# Placa_1.net
KiCad netlist of a schematic drawn in EAGLE
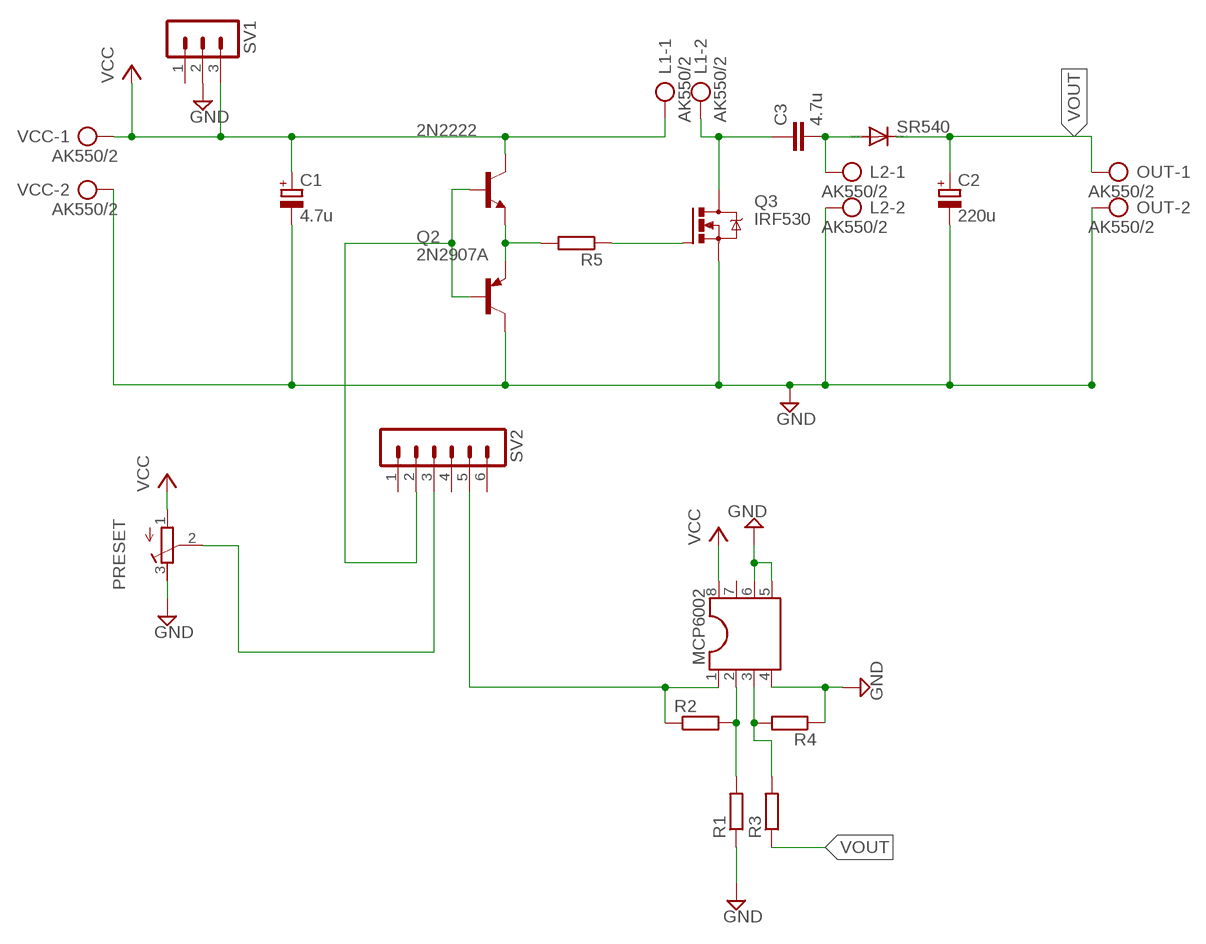
[diagram p0: schematic, sheet 1]

(export (version "E")
  (design (tool "Eeschema 10.0.6"))
  (components
    (comp (ref "2N2222")
      (value "2N2222-NPN-TO92-EBC")
      (footprint "eagle-import:TO92-EBC")
      (libsource (lib "eagle-import") (part "-NPN-TO92-EBC2N2222"))
    )
    (comp (ref "C1")
      (value "4.7u")
      (footprint "eagle-import:E5-8,5")
      (libsource (lib "eagle-import") (part "CPOL-EUE5-8.5"))
    )
    (comp (ref "C2")
      (value "220u")
      (footprint "eagle-import:E5-8,5")
      (libsource (lib "eagle-import") (part "CPOL-EUE5-8.5"))
    )
    (comp (ref "C3")
      (value "4.7u")
      (footprint "eagle-import:C075-052X106")
      (libsource (lib "eagle-import") (part "C-EU075-052X106"))
    )
    (comp (ref "L1")
      (value "AK550/2")
      (footprint "eagle-import:AK550_2")
      (libsource (lib "eagle-import") (part "AK550/2"))
    )
    (comp (ref "L2")
      (value "AK550/2")
      (footprint "eagle-import:AK550_2")
      (libsource (lib "eagle-import") (part "AK550/2"))
    )
    (comp (ref "MCP6002")
      (value "DIL8")
      (footprint "eagle-import:DIL08")
      (libsource (lib "eagle-import") (part "DIL8"))
    )
    (comp (ref "OUT")
      (value "AK550/2")
      (footprint "eagle-import:AK550_2")
      (libsource (lib "eagle-import") (part "AK550/2"))
    )
    (comp (ref "PRESET")
      (value "R-TRIMM64W")
      (footprint "eagle-import:RTRIM64W")
      (libsource (lib "eagle-import") (part "R-TRIMM64W"))
    )
    (comp (ref "Q2")
      (value "2N2907A")
      (footprint "eagle-import:TO18")
      (libsource (lib "eagle-import") (part "2N2907A"))
    )
    (comp (ref "Q3")
      (value "IRF530")
      (footprint "eagle-import:TO220BV")
      (libsource (lib "eagle-import") (part "IRF530"))
    )
    (comp (ref "R1")
      (value "R-EU_0207/10")
      (footprint "eagle-import:0207_10")
      (libsource (lib "eagle-import") (part "R-EU_0207/10"))
    )
    (comp (ref "R2")
      (value "R-EU_0207/10")
      (footprint "eagle-import:0207_10")
      (libsource (lib "eagle-import") (part "R-EU_0207/10"))
    )
    (comp (ref "R3")
      (value "R-EU_0207/10")
      (footprint "eagle-import:0207_10")
      (libsource (lib "eagle-import") (part "R-EU_0207/10"))
    )
    (comp (ref "R4")
      (value "R-EU_0207/10")
      (footprint "eagle-import:0207_10")
      (libsource (lib "eagle-import") (part "R-EU_0207/10"))
    )
    (comp (ref "R5")
      (value "R-EU_0207/10")
      (footprint "eagle-import:0207_10")
      (libsource (lib "eagle-import") (part "R-EU_0207/10"))
    )
    (comp (ref "SR540")
      (value "DIODE-DO27-15")
      (footprint "eagle-import:DO27-15")
      (libsource (lib "eagle-import") (part "DIODE-DO27-15"))
    )
    (comp (ref "SV1")
      (value "MA03-1")
      (footprint "eagle-import:MA03-1")
      (libsource (lib "eagle-import") (part "MA03-1"))
    )
    (comp (ref "SV2")
      (value "MA06-1")
      (footprint "eagle-import:MA06-1")
      (libsource (lib "eagle-import") (part "MA06-1"))
    )
    (comp (ref "VCC")
      (value "AK550/2")
      (footprint "eagle-import:AK550_2")
      (libsource (lib "eagle-import") (part "AK550/2"))
    )
  )
  (nets
    (net (code "1") (name "GND") (class "Default")
      (node (ref "C1") (pin "-") (pinfunction "-_-") (pintype "passive"))
      (node (ref "C2") (pin "-") (pinfunction "-_-") (pintype "passive"))
      (node (ref "L2") (pin "2") (pinfunction "KL_2") (pintype "passive"))
      (node (ref "MCP6002") (pin "4") (pinfunction "4_4") (pintype "passive"))
      (node (ref "MCP6002") (pin "5") (pinfunction "5_5") (pintype "passive"))
      (node (ref "MCP6002") (pin "6") (pinfunction "6_6") (pintype "passive"))
      (node (ref "OUT") (pin "2") (pinfunction "KL_2") (pintype "passive"))
      (node (ref "PRESET") (pin "3") (pinfunction "E_3") (pintype "passive"))
      (node (ref "Q2") (pin "3") (pinfunction "C_3") (pintype "passive"))
      (node (ref "Q3") (pin "S") (pinfunction "S_S") (pintype "passive"))
      (node (ref "R1") (pin "1") (pinfunction "1_1") (pintype "passive"))
      (node (ref "R4") (pin "1") (pinfunction "1_1") (pintype "passive"))
      (node (ref "SV1") (pin "2") (pinfunction "2_2") (pintype "passive"))
      (node (ref "VCC") (pin "2") (pinfunction "KL_2") (pintype "passive"))
    )
    (net (code "2") (name "Net-(L1B-KL)") (class "Default")
      (node (ref "C3") (pin "1") (pinfunction "1_1") (pintype "passive"))
      (node (ref "L1") (pin "2") (pinfunction "KL_2") (pintype "passive"))
      (node (ref "Q3") (pin "D") (pinfunction "D_D") (pintype "passive"))
    )
    (net (code "3") (name "Net-(L2A-KL)") (class "Default")
      (node (ref "C3") (pin "2") (pinfunction "2_2") (pintype "passive"))
      (node (ref "L2") (pin "1") (pinfunction "KL_1") (pintype "passive"))
      (node (ref "SR540") (pin "A") (pinfunction "A_A") (pintype "passive"))
    )
    (net (code "4") (name "Net-(MCP6002-Pad1)") (class "Default")
      (node (ref "MCP6002") (pin "1") (pinfunction "1_1") (pintype "passive"))
      (node (ref "R2") (pin "1") (pinfunction "1_1") (pintype "passive"))
      (node (ref "SV2") (pin "5") (pinfunction "5_5") (pintype "passive"))
    )
    (net (code "5") (name "Net-(MCP6002-Pad2)") (class "Default")
      (node (ref "MCP6002") (pin "2") (pinfunction "2_2") (pintype "passive"))
      (node (ref "R1") (pin "2") (pinfunction "2_2") (pintype "passive"))
      (node (ref "R2") (pin "2") (pinfunction "2_2") (pintype "passive"))
    )
    (net (code "6") (name "Net-(MCP6002-Pad3)") (class "Default")
      (node (ref "MCP6002") (pin "3") (pinfunction "3_3") (pintype "passive"))
      (node (ref "R3") (pin "2") (pinfunction "2_2") (pintype "passive"))
      (node (ref "R4") (pin "2") (pinfunction "2_2") (pintype "passive"))
    )
    (net (code "7") (name "Net-(PRESET-S)") (class "Default")
      (node (ref "PRESET") (pin "2") (pinfunction "S_2") (pintype "passive"))
      (node (ref "SV2") (pin "3") (pinfunction "3_3") (pintype "passive"))
    )
    (net (code "8") (name "Net-(Q2-B)") (class "Default")
      (node (ref "2N2222") (pin "B") (pinfunction "B_B") (pintype "passive"))
      (node (ref "Q2") (pin "2") (pinfunction "B_2") (pintype "passive"))
      (node (ref "SV2") (pin "2") (pinfunction "2_2") (pintype "passive"))
    )
    (net (code "9") (name "Net-(Q2-E)") (class "Default")
      (node (ref "2N2222") (pin "E") (pinfunction "E_E") (pintype "passive"))
      (node (ref "Q2") (pin "1") (pinfunction "E_1") (pintype "passive"))
      (node (ref "R5") (pin "2") (pinfunction "2_2") (pintype "passive"))
    )
    (net (code "10") (name "Net-(Q3-PadG)") (class "Default")
      (node (ref "Q3") (pin "G") (pinfunction "G_G") (pintype "passive"))
      (node (ref "R5") (pin "1") (pinfunction "1_1") (pintype "passive"))
    )
    (net (code "11") (name "VCC") (class "Default")
      (node (ref "2N2222") (pin "C") (pinfunction "C_C") (pintype "passive"))
      (node (ref "C1") (pin "+") (pinfunction "+_+") (pintype "passive"))
      (node (ref "L1") (pin "1") (pinfunction "KL_1") (pintype "passive"))
      (node (ref "MCP6002") (pin "8") (pinfunction "8_8") (pintype "passive"))
      (node (ref "PRESET") (pin "1") (pinfunction "A_1") (pintype "passive"))
      (node (ref "SV1") (pin "3") (pinfunction "3_3") (pintype "passive"))
      (node (ref "VCC") (pin "1") (pinfunction "KL_1") (pintype "passive"))
    )
    (net (code "12") (name "VOUT") (class "Default")
      (node (ref "C2") (pin "+") (pinfunction "+_+") (pintype "passive"))
      (node (ref "OUT") (pin "1") (pinfunction "KL_1") (pintype "passive"))
      (node (ref "R3") (pin "1") (pinfunction "1_1") (pintype "passive"))
      (node (ref "SR540") (pin "C") (pinfunction "C_C") (pintype "passive"))
    )
    (net (code "13") (name "unconnected-(MCP6002-Pad7)") (class "Default")
      (node (ref "MCP6002") (pin "7") (pinfunction "7_7") (pintype "passive"))
    )
    (net (code "14") (name "unconnected-(SV1-Pad1)") (class "Default")
      (node (ref "SV1") (pin "1") (pinfunction "1_1") (pintype "passive"))
    )
    (net (code "15") (name "unconnected-(SV2-Pad1)") (class "Default")
      (node (ref "SV2") (pin "1") (pinfunction "1_1") (pintype "passive"))
    )
    (net (code "16") (name "unconnected-(SV2-Pad4)") (class "Default")
      (node (ref "SV2") (pin "4") (pinfunction "4_4") (pintype "passive"))
    )
    (net (code "17") (name "unconnected-(SV2-Pad6)") (class "Default")
      (node (ref "SV2") (pin "6") (pinfunction "6_6") (pintype "passive"))
    )
  )
)
